# Rocketometer2148_MPU6050.net
KiCad netlist of a schematic drawn in EAGLE
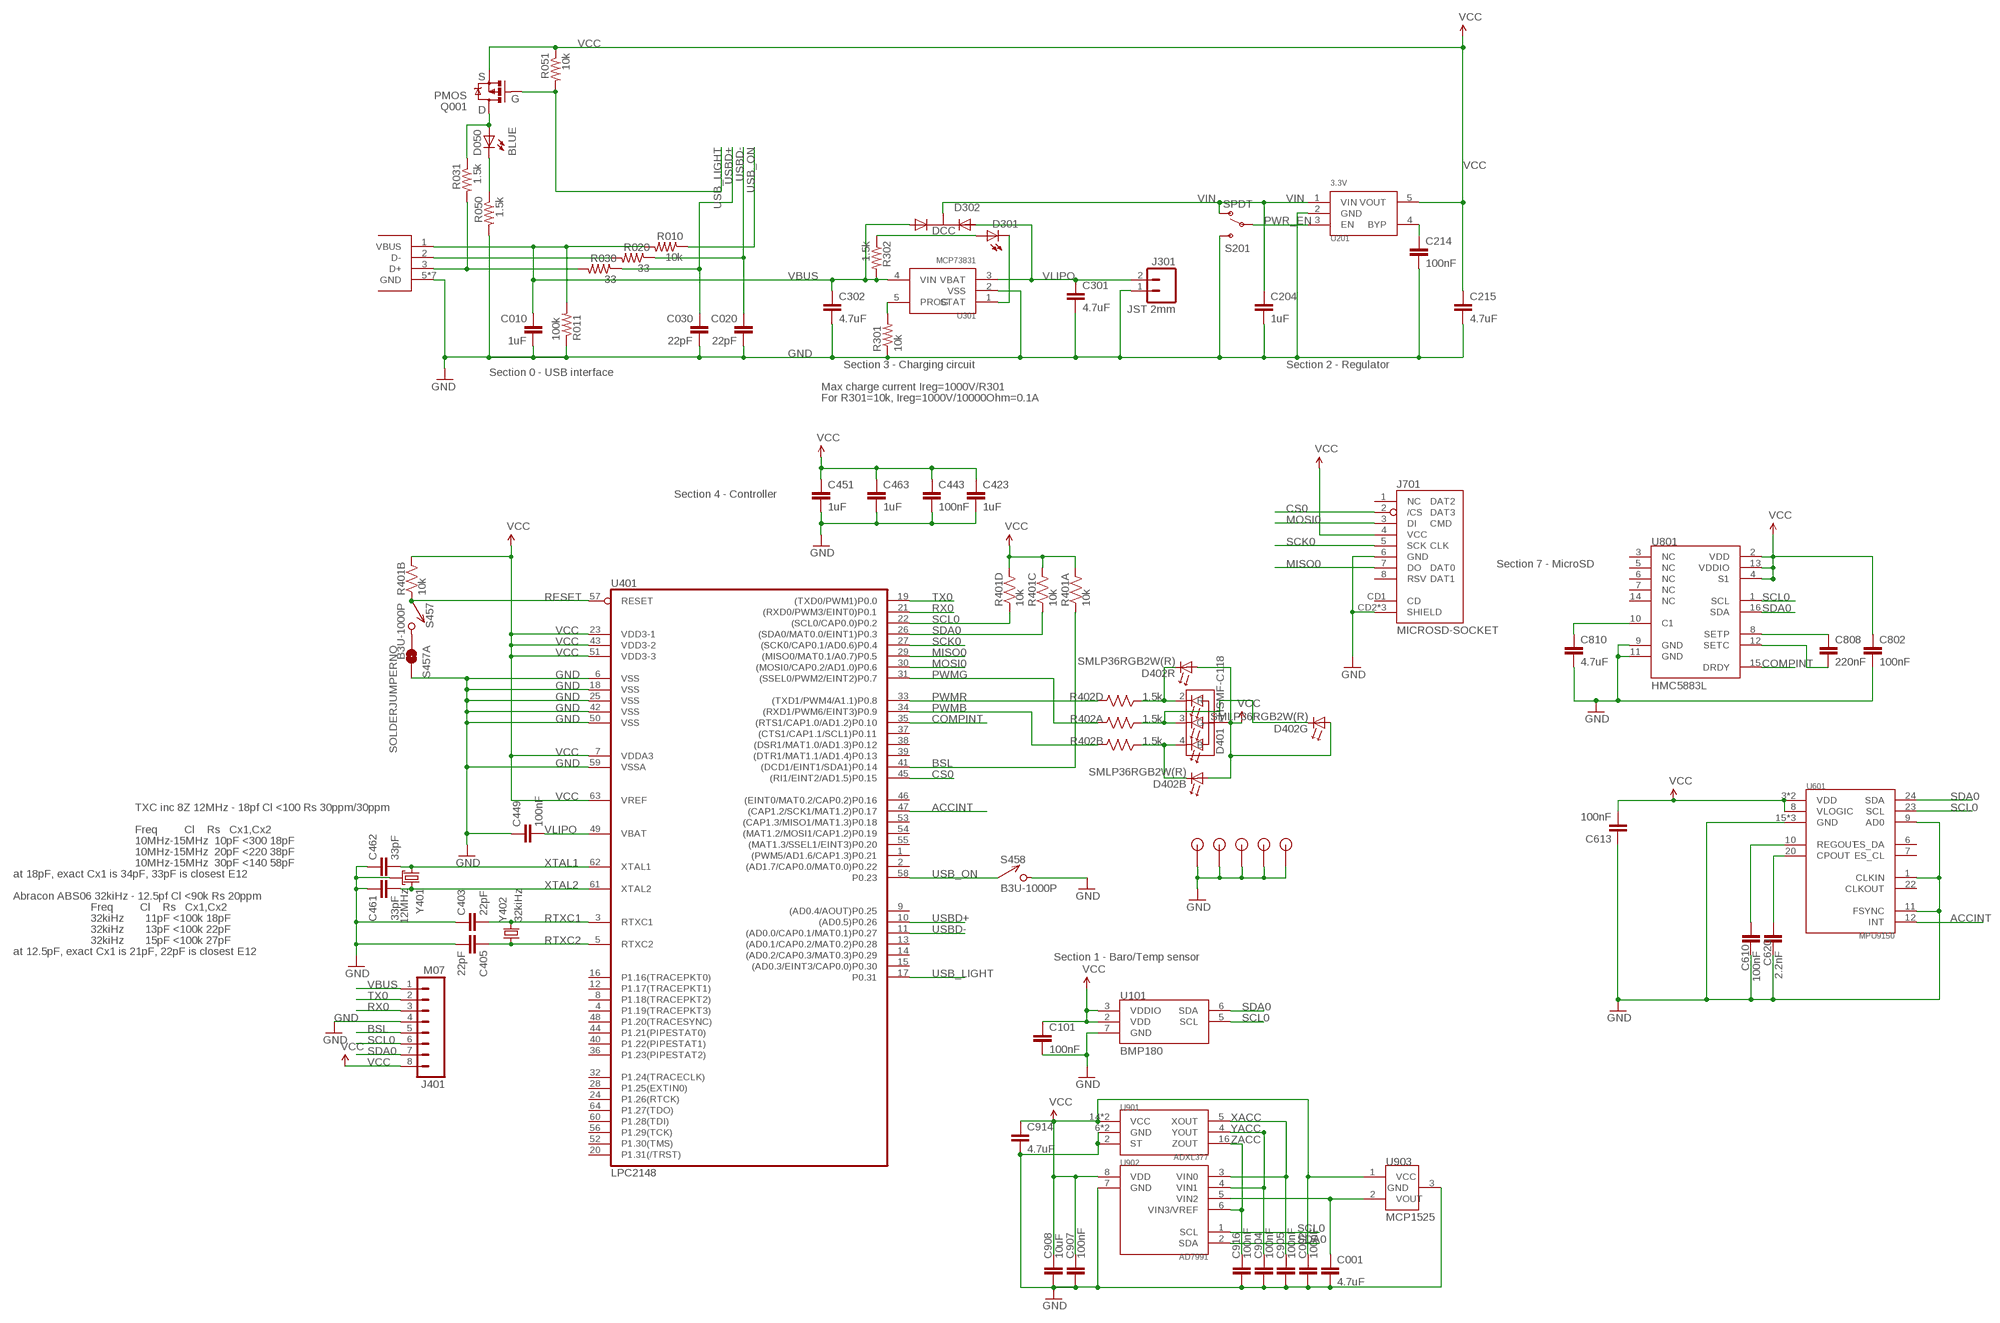
[diagram p0: schematic, sheet 1]

(export (version "E")
  (design (tool "Eeschema 10.0.6"))
  (components
    (comp (ref "C001")
      (value "4.7uF")
      (footprint "eagle-import:0402-CAP")
      (libsource (lib "eagle-import") (part "CAP0402-CAP"))
    )
    (comp (ref "C002")
      (value "100nF")
      (footprint "eagle-import:0402-CAP")
      (libsource (lib "eagle-import") (part "SparkFun-Passives_CAP0402-CAP"))
    )
    (comp (ref "C010")
      (value "1uF")
      (footprint "eagle-import:0402-CAP")
      (libsource (lib "eagle-import") (part "CAP0402-CAP"))
    )
    (comp (ref "C020")
      (value "22pF")
      (footprint "eagle-import:0402-CAP")
      (libsource (lib "eagle-import") (part "CAP0402-CAP"))
    )
    (comp (ref "C030")
      (value "22pF")
      (footprint "eagle-import:0402-CAP")
      (libsource (lib "eagle-import") (part "CAP0402-CAP"))
    )
    (comp (ref "C101")
      (value "100nF")
      (footprint "eagle-import:0402-CAP")
      (libsource (lib "eagle-import") (part "CAP0402-CAP"))
    )
    (comp (ref "C204")
      (value "1uF")
      (footprint "eagle-import:0402-CAP")
      (libsource (lib "eagle-import") (part "CAP0402-CAP"))
    )
    (comp (ref "C214")
      (value "100nF")
      (footprint "eagle-import:0402-CAP")
      (libsource (lib "eagle-import") (part "CAP0402-CAP"))
    )
    (comp (ref "C215")
      (value "4.7uF")
      (footprint "eagle-import:0402-CAP")
      (libsource (lib "eagle-import") (part "CAP0402-CAP"))
    )
    (comp (ref "C301")
      (value "4.7uF")
      (footprint "eagle-import:0402-CAP")
      (libsource (lib "eagle-import") (part "CAP0402-CAP"))
    )
    (comp (ref "C302")
      (value "4.7uF")
      (footprint "eagle-import:0402-CAP")
      (libsource (lib "eagle-import") (part "CAP0402-CAP"))
    )
    (comp (ref "C403")
      (value "22pF")
      (footprint "eagle-import:0402-CAP")
      (libsource (lib "eagle-import") (part "CAP0402-CAP"))
    )
    (comp (ref "C405")
      (value "22pF")
      (footprint "eagle-import:0402-CAP")
      (libsource (lib "eagle-import") (part "CAP0402-CAP"))
    )
    (comp (ref "C423")
      (value "1uF")
      (footprint "eagle-import:0402-CAP")
      (libsource (lib "eagle-import") (part "CAP0402-CAP"))
    )
    (comp (ref "C443")
      (value "100nF")
      (footprint "eagle-import:0402-CAP")
      (libsource (lib "eagle-import") (part "CAP0402-CAP"))
    )
    (comp (ref "C449")
      (value "100nF")
      (footprint "eagle-import:0402-CAP")
      (libsource (lib "eagle-import") (part "CAP0402-CAP"))
    )
    (comp (ref "C451")
      (value "1uF")
      (footprint "eagle-import:0402-CAP")
      (libsource (lib "eagle-import") (part "CAP0402-CAP"))
    )
    (comp (ref "C461")
      (value "33pF")
      (footprint "eagle-import:0402-CAP")
      (libsource (lib "eagle-import") (part "CAP0402-CAP"))
    )
    (comp (ref "C462")
      (value "33pF")
      (footprint "eagle-import:0402-CAP")
      (libsource (lib "eagle-import") (part "CAP0402-CAP"))
    )
    (comp (ref "C463")
      (value "1uF")
      (footprint "eagle-import:0402-CAP")
      (libsource (lib "eagle-import") (part "CAP0402-CAP"))
    )
    (comp (ref "C610")
      (value "100nF")
      (footprint "eagle-import:0402-CAP")
      (libsource (lib "eagle-import") (part "CAP0402-CAP"))
    )
    (comp (ref "C613")
      (value "100nF")
      (footprint "eagle-import:0402-CAP")
      (libsource (lib "eagle-import") (part "CAP0402-CAP"))
    )
    (comp (ref "C620")
      (value "2.2nF")
      (footprint "eagle-import:0402-CAP")
      (libsource (lib "eagle-import") (part "CAP0402-CAP"))
    )
    (comp (ref "C802")
      (value "100nF")
      (footprint "eagle-import:0402-CAP")
      (libsource (lib "eagle-import") (part "CAP0402-CAP"))
    )
    (comp (ref "C808")
      (value "220nF")
      (footprint "eagle-import:0402-CAP")
      (libsource (lib "eagle-import") (part "CAP0402-CAP"))
    )
    (comp (ref "C810")
      (value "4.7uF")
      (footprint "eagle-import:0402-CAP")
      (libsource (lib "eagle-import") (part "CAP0402-CAP"))
    )
    (comp (ref "C904")
      (value "100nF")
      (footprint "eagle-import:0402-CAP")
      (libsource (lib "eagle-import") (part "CAP0402-CAP"))
    )
    (comp (ref "C905")
      (value "100nF")
      (footprint "eagle-import:0402-CAP")
      (libsource (lib "eagle-import") (part "CAP0402-CAP"))
    )
    (comp (ref "C907")
      (value "100nF")
      (footprint "eagle-import:0402-CAP")
      (libsource (lib "eagle-import") (part "SparkFun-Passives_CAP0402-CAP"))
    )
    (comp (ref "C908")
      (value "10uF")
      (footprint "eagle-import:0603-CAP")
      (libsource (lib "eagle-import") (part "CAP0603-CAP"))
    )
    (comp (ref "C914")
      (value "4.7uF")
      (footprint "eagle-import:0402-CAP")
      (libsource (lib "eagle-import") (part "CAP0402-CAP"))
    )
    (comp (ref "C916")
      (value "100nF")
      (footprint "eagle-import:0402-CAP")
      (libsource (lib "eagle-import") (part "CAP0402-CAP"))
    )
    (comp (ref "D050")
      (value "BLUE")
      (footprint "eagle-import:LED-0603")
      (libsource (lib "eagle-import") (part "LED0603"))
    )
    (comp (ref "D301")
      (value "YELLOW")
      (footprint "eagle-import:LED-0603")
      (libsource (lib "eagle-import") (part "LED0603"))
    )
    (comp (ref "D302")
      (value "DCC")
      (footprint "eagle-import:SOT-23-3")
      (libsource (lib "eagle-import") (part "PMEG2005CT"))
    )
    (comp (ref "D401")
      (value "HSMF-C118")
      (footprint "eagle-import:HSMF-C118")
      (libsource (lib "eagle-import") (part "HSMF-C118"))
    )
    (comp (ref "D402")
      (value "SMLP36RGB2W(R)")
      (footprint "eagle-import:SMLP36")
      (libsource (lib "eagle-import") (part "SMLP36RGB2W(R)"))
    )
    (comp (ref "J001")
      (value "USB_MICROB_JST")
      (footprint "eagle-import:UB-MC5BR3-SD204-4S")
      (libsource (lib "eagle-import") (part "USB_MICROB_JST"))
    )
    (comp (ref "J301")
      (value "JST 2mm")
      (footprint "eagle-import:JST-2-SMD")
      (libsource (lib "eagle-import") (part "M02-JST-2MM-SMT"))
    )
    (comp (ref "J401")
      (value "M07")
      (footprint "eagle-import:1X08")
      (libsource (lib "eagle-import") (part "M081X08"))
    )
    (comp (ref "J701")
      (value "MICROSD-SOCKET")
      (footprint "eagle-import:MICROSD-SOCKET-PP")
      (libsource (lib "eagle-import") (part "MICROSD-SOCKET"))
    )
    (comp (ref "JP1")
      (value "STANDOFF")
      (footprint "eagle-import:STANDOFF")
      (libsource (lib "eagle-import") (part "STANDOFF"))
    )
    (comp (ref "JP2")
      (value "STANDOFF")
      (footprint "eagle-import:STANDOFF")
      (libsource (lib "eagle-import") (part "STANDOFF"))
    )
    (comp (ref "JP3")
      (value "STANDOFF")
      (footprint "eagle-import:STANDOFF")
      (libsource (lib "eagle-import") (part "STANDOFF"))
    )
    (comp (ref "JP4")
      (value "STANDOFF")
      (footprint "eagle-import:STANDOFF")
      (libsource (lib "eagle-import") (part "STANDOFF"))
    )
    (comp (ref "JP5")
      (value "STANDOFF")
      (footprint "eagle-import:STANDOFF")
      (libsource (lib "eagle-import") (part "STANDOFF"))
    )
    (comp (ref "Q001")
      (value "PMOS")
      (footprint "eagle-import:SOT23-3")
      (libsource (lib "eagle-import") (part "MOSFET-PCHANNELSMD"))
    )
    (comp (ref "R010")
      (value "10k")
      (footprint "eagle-import:0402-RES")
      (libsource (lib "eagle-import") (part "RESISTOR0402-RES"))
    )
    (comp (ref "R011")
      (value "100k")
      (footprint "eagle-import:0402-RES")
      (libsource (lib "eagle-import") (part "RESISTOR0402-RES"))
    )
    (comp (ref "R020")
      (value "33")
      (footprint "eagle-import:0402-RES")
      (libsource (lib "eagle-import") (part "RESISTOR0402-RES"))
    )
    (comp (ref "R030")
      (value "33")
      (footprint "eagle-import:0402-RES")
      (libsource (lib "eagle-import") (part "RESISTOR0402-RES"))
    )
    (comp (ref "R031")
      (value "1.5k")
      (footprint "eagle-import:0402-RES")
      (libsource (lib "eagle-import") (part "RESISTOR0402-RES"))
    )
    (comp (ref "R050")
      (value "1.5k")
      (footprint "eagle-import:0402-RES")
      (libsource (lib "eagle-import") (part "RESISTOR0402-RES"))
    )
    (comp (ref "R051")
      (value "10k")
      (footprint "eagle-import:0402-RES")
      (libsource (lib "eagle-import") (part "RESISTOR0402-RES"))
    )
    (comp (ref "R301")
      (value "10k")
      (footprint "eagle-import:0402-RES")
      (libsource (lib "eagle-import") (part "RESISTOR0402-RES"))
    )
    (comp (ref "R302")
      (value "1.5k")
      (footprint "eagle-import:0402-RES")
      (libsource (lib "eagle-import") (part "RESISTOR0402-RES"))
    )
    (comp (ref "R401")
      (value "10k")
      (footprint "eagle-import:CRA04")
      (fields (field (name "DIGIKEY") "CRA4S810KCT-ND"))
      (libsource (lib "eagle-import") (part "RP404"))
    )
    (comp (ref "R402")
      (value "1.5k")
      (footprint "eagle-import:CRA04")
      (fields (field (name "DIGIKEY") "CRA4S81.5KCT-ND"))
      (libsource (lib "eagle-import") (part "RP404"))
    )
    (comp (ref "S201")
      (value "SPDT")
      (footprint "eagle-import:AYZ0202")
      (libsource (lib "eagle-import") (part "SWITCH-SPSTSMD"))
    )
    (comp (ref "S457")
      (value "B3U-1000P")
      (footprint "eagle-import:B3U-1000P")
      (libsource (lib "eagle-import") (part "B3U-1000P"))
    )
    (comp (ref "S457A")
      (value "SOLDERJUMPERNO")
      (footprint "eagle-import:SJ_2S-NO")
      (libsource (lib "eagle-import") (part "SOLDERJUMPERNO"))
    )
    (comp (ref "S458")
      (value "B3U-1000P")
      (footprint "eagle-import:B3U-1000P")
      (libsource (lib "eagle-import") (part "B3U-1000P"))
    )
    (comp (ref "U101")
      (value "BMP180")
      (footprint "eagle-import:BMP180")
      (libsource (lib "eagle-import") (part "BMP180"))
    )
    (comp (ref "U201")
      (value "3.3V")
      (footprint "eagle-import:SOT-23-5")
      (libsource (lib "eagle-import") (part "MIC5319D5"))
    )
    (comp (ref "U301")
      (value "MCP73831")
      (footprint "eagle-import:SOT-23-5")
      (libsource (lib "eagle-import") (part "MCP73831"))
    )
    (comp (ref "U401")
      (value "LPC2148")
      (footprint "eagle-import:SQFP-S-10X10-64")
      (libsource (lib "eagle-import") (part "LPC213X"))
    )
    (comp (ref "U601")
      (value "MPU9150")
      (footprint "eagle-import:LLGA24")
      (libsource (lib "eagle-import") (part "MPU9150"))
    )
    (comp (ref "U801")
      (value "HMC5883L")
      (footprint "eagle-import:16LPCC")
      (libsource (lib "eagle-import") (part "HMC5883LSMD"))
    )
    (comp (ref "U901")
      (value "ADXL377")
      (footprint "eagle-import:ADXL377")
      (libsource (lib "eagle-import") (part "ADXL377"))
    )
    (comp (ref "U902")
      (value "AD7991")
      (footprint "eagle-import:SOT-23-8")
      (libsource (lib "eagle-import") (part "AD799X"))
    )
    (comp (ref "U903")
      (value "MCP1525")
      (footprint "eagle-import:SOT-23-3")
      (libsource (lib "eagle-import") (part "MCP1525"))
    )
    (comp (ref "Y401")
      (value "12MHz")
      (footprint "eagle-import:CRYSTAL_SMD_2MM_2_5MM")
      (libsource (lib "eagle-import") (part "CX2520"))
    )
    (comp (ref "Y402")
      (value "32kiHz")
      (footprint "eagle-import:ABS06")
      (libsource (lib "eagle-import") (part "ABS06"))
    )
  )
  (nets
    (net (code "1") (name "/ACCINT") (class "Default")
      (node (ref "U401") (pin "47") (pinfunction "(CAP1.2/SCK1/MAT1.2)P0.17_47") (pintype "bidirectional"))
      (node (ref "U601") (pin "12") (pinfunction "INT_12") (pintype "bidirectional"))
    )
    (net (code "2") (name "/BSL") (class "Default")
      (node (ref "J401") (pin "5") (pinfunction "5_5") (pintype "passive"))
      (node (ref "R401") (pin "1") (pinfunction "1_1") (pintype "passive"))
      (node (ref "U401") (pin "41") (pinfunction "(DCD1/EINT1/SDA1)P0.14_41") (pintype "bidirectional"))
    )
    (net (code "3") (name "/COMPINT") (class "Default")
      (node (ref "U401") (pin "35") (pinfunction "(RTS1/CAP1.0/AD1.2)P0.10_35") (pintype "bidirectional"))
      (node (ref "U801") (pin "15") (pinfunction "DRDY_15") (pintype "bidirectional"))
    )
    (net (code "4") (name "/CS0") (class "Default")
      (node (ref "J701") (pin "2") (pinfunction "/CS_2") (pintype "bidirectional"))
      (node (ref "U401") (pin "45") (pinfunction "(RI1/EINT2/AD1.5)P0.15_45") (pintype "bidirectional"))
    )
    (net (code "5") (name "/MISO0") (class "Default")
      (node (ref "J701") (pin "7") (pinfunction "DO_7") (pintype "bidirectional"))
      (node (ref "U401") (pin "29") (pinfunction "(MISO0/MAT0.1/A0.7)P0.5_29") (pintype "bidirectional"))
    )
    (net (code "6") (name "/MOSI0") (class "Default")
      (node (ref "J701") (pin "3") (pinfunction "DI_3") (pintype "bidirectional"))
      (node (ref "U401") (pin "30") (pinfunction "(MOSI0/CAP0.2/AD1.0)P0.6_30") (pintype "bidirectional"))
    )
    (net (code "7") (name "/PWMB") (class "Default")
      (node (ref "R402") (pin "7") (pinfunction "2_7") (pintype "passive"))
      (node (ref "U401") (pin "34") (pinfunction "(RXD1/PWM6/EINT3)P0.9_34") (pintype "bidirectional"))
    )
    (net (code "8") (name "/PWMG") (class "Default")
      (node (ref "R402") (pin "8") (pinfunction "2_8") (pintype "passive"))
      (node (ref "U401") (pin "31") (pinfunction "(SSEL0/PWM2/EINT2)P0.7_31") (pintype "bidirectional"))
    )
    (net (code "9") (name "/PWMR") (class "Default")
      (node (ref "R402") (pin "5") (pinfunction "2_5") (pintype "passive"))
      (node (ref "U401") (pin "33") (pinfunction "(TXD1/PWM4/A1.1)P0.8_33") (pintype "bidirectional"))
    )
    (net (code "10") (name "/PWR_EN") (class "Default")
      (node (ref "S201") (pin "2") (pinfunction "P_2") (pintype "passive"))
      (node (ref "U201") (pin "3") (pinfunction "EN_3") (pintype "bidirectional"))
    )
    (net (code "11") (name "/RESET") (class "Default")
      (node (ref "R401") (pin "2") (pinfunction "1_2") (pintype "passive"))
      (node (ref "S457") (pin "P$1") (pinfunction "1_P$1") (pintype "bidirectional"))
      (node (ref "U401") (pin "57") (pinfunction "RESET_57") (pintype "input"))
    )
    (net (code "12") (name "/RTXC1") (class "Default")
      (node (ref "C403") (pin "2") (pinfunction "2_2") (pintype "passive"))
      (node (ref "U401") (pin "3") (pinfunction "RTXC1_3") (pintype "input"))
      (node (ref "Y402") (pin "2") (pinfunction "2_2") (pintype "passive"))
    )
    (net (code "13") (name "/RTXC2") (class "Default")
      (node (ref "C405") (pin "1") (pinfunction "1_1") (pintype "passive"))
      (node (ref "U401") (pin "5") (pinfunction "RTXC2_5") (pintype "output"))
      (node (ref "Y402") (pin "1") (pinfunction "1_1") (pintype "passive"))
    )
    (net (code "14") (name "/RX0") (class "Default")
      (node (ref "J401") (pin "3") (pinfunction "3_3") (pintype "passive"))
      (node (ref "U401") (pin "21") (pinfunction "(RXD0/PWM3/EINT0)P0.1_21") (pintype "bidirectional"))
    )
    (net (code "15") (name "/SCK0") (class "Default")
      (node (ref "J701") (pin "5") (pinfunction "SCK_5") (pintype "bidirectional"))
      (node (ref "U401") (pin "27") (pinfunction "(SCK0/CAP0.1/AD0.6)P0.4_27") (pintype "bidirectional"))
    )
    (net (code "16") (name "/SCL0") (class "Default")
      (node (ref "J401") (pin "6") (pinfunction "6_6") (pintype "passive"))
      (node (ref "R401") (pin "4") (pinfunction "1_4") (pintype "passive"))
      (node (ref "U101") (pin "5") (pinfunction "SCL_5") (pintype "input"))
      (node (ref "U401") (pin "22") (pinfunction "(SCL0/CAP0.0)P0.2_22") (pintype "bidirectional"))
      (node (ref "U601") (pin "23") (pinfunction "SCL_23") (pintype "bidirectional"))
      (node (ref "U801") (pin "1") (pinfunction "SCL_1") (pintype "bidirectional"))
      (node (ref "U902") (pin "1") (pinfunction "SCL_1") (pintype "bidirectional"))
    )
    (net (code "17") (name "/SDA0") (class "Default")
      (node (ref "J401") (pin "7") (pinfunction "7_7") (pintype "passive"))
      (node (ref "R401") (pin "3") (pinfunction "1_3") (pintype "passive"))
      (node (ref "U101") (pin "6") (pinfunction "SDA_6") (pintype "bidirectional"))
      (node (ref "U401") (pin "26") (pinfunction "(SDA0/MAT0.0/EINT1)P0.3_26") (pintype "bidirectional"))
      (node (ref "U601") (pin "24") (pinfunction "SDA_24") (pintype "bidirectional"))
      (node (ref "U801") (pin "16") (pinfunction "SDA_16") (pintype "bidirectional"))
      (node (ref "U902") (pin "2") (pinfunction "SDA_2") (pintype "bidirectional"))
    )
    (net (code "18") (name "/TX0") (class "Default")
      (node (ref "J401") (pin "2") (pinfunction "2_2") (pintype "passive"))
      (node (ref "U401") (pin "19") (pinfunction "(TXD0/PWM1)P0.0_19") (pintype "bidirectional"))
    )
    (net (code "19") (name "/USBD+") (class "Default")
      (node (ref "C030") (pin "1") (pinfunction "1_1") (pintype "passive"))
      (node (ref "R030") (pin "1") (pinfunction "1_1") (pintype "passive"))
      (node (ref "U401") (pin "10") (pinfunction "(AD0.5)P0.26_10") (pintype "bidirectional"))
    )
    (net (code "20") (name "/USBD-") (class "Default")
      (node (ref "C020") (pin "1") (pinfunction "1_1") (pintype "passive"))
      (node (ref "R020") (pin "1") (pinfunction "1_1") (pintype "passive"))
      (node (ref "U401") (pin "11") (pinfunction "(AD0.0/CAP0.1/MAT0.1)P0.27_11") (pintype "bidirectional"))
    )
    (net (code "21") (name "/USB_LIGHT") (class "Default")
      (node (ref "Q001") (pin "1") (pinfunction "G_1") (pintype "passive"))
      (node (ref "R051") (pin "2") (pinfunction "2_2") (pintype "passive"))
      (node (ref "U401") (pin "17") (pinfunction "P0.31_17") (pintype "output"))
    )
    (net (code "22") (name "/USB_ON") (class "Default")
      (node (ref "R010") (pin "1") (pinfunction "1_1") (pintype "passive"))
      (node (ref "S458") (pin "P$1") (pinfunction "1_P$1") (pintype "bidirectional"))
      (node (ref "U401") (pin "58") (pinfunction "P0.23_58") (pintype "bidirectional"))
    )
    (net (code "23") (name "/VBUS") (class "Default")
      (node (ref "C010") (pin "1") (pinfunction "1_1") (pintype "passive"))
      (node (ref "C302") (pin "1") (pinfunction "1_1") (pintype "passive"))
      (node (ref "D302") (pin "1") (pinfunction "A1_1") (pintype "passive"))
      (node (ref "J001") (pin "1") (pinfunction "VBUS_1") (pintype "bidirectional"))
      (node (ref "J401") (pin "1") (pinfunction "1_1") (pintype "passive"))
      (node (ref "R010") (pin "2") (pinfunction "2_2") (pintype "passive"))
      (node (ref "R011") (pin "2") (pinfunction "2_2") (pintype "passive"))
      (node (ref "R302") (pin "2") (pinfunction "2_2") (pintype "passive"))
      (node (ref "U301") (pin "4") (pinfunction "VIN_4") (pintype "power_in"))
    )
    (net (code "24") (name "/VIN") (class "Default")
      (node (ref "C204") (pin "1") (pinfunction "1_1") (pintype "passive"))
      (node (ref "D302") (pin "3") (pinfunction "K_3") (pintype "passive"))
      (node (ref "S201") (pin "1") (pinfunction "O_1") (pintype "passive"))
      (node (ref "U201") (pin "1") (pinfunction "VIN_1") (pintype "bidirectional"))
    )
    (net (code "25") (name "/VLIPO") (class "Default")
      (node (ref "C301") (pin "1") (pinfunction "1_1") (pintype "passive"))
      (node (ref "C449") (pin "2") (pinfunction "2_2") (pintype "passive"))
      (node (ref "D302") (pin "2") (pinfunction "A2_2") (pintype "passive"))
      (node (ref "J301") (pin "2") (pinfunction "2_2") (pintype "passive"))
      (node (ref "U301") (pin "3") (pinfunction "VBAT_3") (pintype "power_in"))
      (node (ref "U401") (pin "49") (pinfunction "VBAT_49") (pintype "power_in"))
    )
    (net (code "26") (name "/XACC") (class "Default")
      (node (ref "C905") (pin "1") (pinfunction "1_1") (pintype "passive"))
      (node (ref "U901") (pin "5") (pinfunction "XOUT_5") (pintype "bidirectional"))
      (node (ref "U902") (pin "3") (pinfunction "VIN0_3") (pintype "bidirectional"))
    )
    (net (code "27") (name "/XTAL1") (class "Default")
      (node (ref "C462") (pin "2") (pinfunction "2_2") (pintype "passive"))
      (node (ref "U401") (pin "62") (pinfunction "XTAL1_62") (pintype "input"))
      (node (ref "Y401") (pin "1") (pinfunction "1_1") (pintype "passive"))
    )
    (net (code "28") (name "/XTAL2") (class "Default")
      (node (ref "C461") (pin "2") (pinfunction "2_2") (pintype "passive"))
      (node (ref "U401") (pin "61") (pinfunction "XTAL2_61") (pintype "output"))
      (node (ref "Y401") (pin "3") (pinfunction "2_3") (pintype "passive"))
    )
    (net (code "29") (name "/YACC") (class "Default")
      (node (ref "C904") (pin "1") (pinfunction "1_1") (pintype "passive"))
      (node (ref "U901") (pin "4") (pinfunction "YOUT_4") (pintype "bidirectional"))
      (node (ref "U902") (pin "4") (pinfunction "VIN1_4") (pintype "bidirectional"))
    )
    (net (code "30") (name "/ZACC") (class "Default")
      (node (ref "C916") (pin "1") (pinfunction "1_1") (pintype "passive"))
      (node (ref "U901") (pin "16") (pinfunction "ZOUT_16") (pintype "bidirectional"))
      (node (ref "U902") (pin "6") (pinfunction "VIN3/VREF_6") (pintype "bidirectional"))
    )
    (net (code "31") (name "GND") (class "Default")
      (node (ref "C001") (pin "2") (pinfunction "2_2") (pintype "passive"))
      (node (ref "C002") (pin "2") (pinfunction "2_2") (pintype "passive"))
      (node (ref "C010") (pin "2") (pinfunction "2_2") (pintype "passive"))
      (node (ref "C020") (pin "2") (pinfunction "2_2") (pintype "passive"))
      (node (ref "C030") (pin "2") (pinfunction "2_2") (pintype "passive"))
      (node (ref "C101") (pin "2") (pinfunction "2_2") (pintype "passive"))
      (node (ref "C204") (pin "2") (pinfunction "2_2") (pintype "passive"))
      (node (ref "C214") (pin "2") (pinfunction "2_2") (pintype "passive"))
      (node (ref "C215") (pin "2") (pinfunction "2_2") (pintype "passive"))
      (node (ref "C301") (pin "2") (pinfunction "2_2") (pintype "passive"))
      (node (ref "C302") (pin "2") (pinfunction "2_2") (pintype "passive"))
      (node (ref "C403") (pin "1") (pinfunction "1_1") (pintype "passive"))
      (node (ref "C405") (pin "2") (pinfunction "2_2") (pintype "passive"))
      (node (ref "C423") (pin "2") (pinfunction "2_2") (pintype "passive"))
      (node (ref "C443") (pin "2") (pinfunction "2_2") (pintype "passive"))
      (node (ref "C449") (pin "1") (pinfunction "1_1") (pintype "passive"))
      (node (ref "C451") (pin "2") (pinfunction "2_2") (pintype "passive"))
      (node (ref "C461") (pin "1") (pinfunction "1_1") (pintype "passive"))
      (node (ref "C462") (pin "1") (pinfunction "1_1") (pintype "passive"))
      (node (ref "C463") (pin "2") (pinfunction "2_2") (pintype "passive"))
      (node (ref "C610") (pin "2") (pinfunction "2_2") (pintype "passive"))
      (node (ref "C613") (pin "1") (pinfunction "1_1") (pintype "passive"))
      (node (ref "C620") (pin "1") (pinfunction "1_1") (pintype "passive"))
      (node (ref "C802") (pin "2") (pinfunction "2_2") (pintype "passive"))
      (node (ref "C810") (pin "2") (pinfunction "2_2") (pintype "passive"))
      (node (ref "C904") (pin "2") (pinfunction "2_2") (pintype "passive"))
      (node (ref "C905") (pin "2") (pinfunction "2_2") (pintype "passive"))
      (node (ref "C907") (pin "2") (pinfunction "2_2") (pintype "passive"))
      (node (ref "C908") (pin "2") (pinfunction "2_2") (pintype "passive"))
      (node (ref "C914") (pin "2") (pinfunction "2_2") (pintype "passive"))
      (node (ref "C916") (pin "2") (pinfunction "2_2") (pintype "passive"))
      (node (ref "J001") (pin "5") (pinfunction "GND_5") (pintype "bidirectional"))
      (node (ref "J001") (pin "P$10") (pinfunction "GND_P$10") (pintype "bidirectional"))
      (node (ref "J001") (pin "P$11") (pinfunction "GND_P$11") (pintype "bidirectional"))
      (node (ref "J001") (pin "P$6") (pinfunction "GND_P$6") (pintype "bidirectional"))
      (node (ref "J001") (pin "P$7") (pinfunction "GND_P$7") (pintype "bidirectional"))
      (node (ref "J001") (pin "P$8") (pinfunction "GND_P$8") (pintype "bidirectional"))
      (node (ref "J001") (pin "P$9") (pinfunction "GND_P$9") (pintype "bidirectional"))
      (node (ref "J301") (pin "1") (pinfunction "1_1") (pintype "passive"))
      (node (ref "J401") (pin "4") (pinfunction "4_4") (pintype "passive"))
      (node (ref "J701") (pin "6") (pinfunction "GND_6") (pintype "bidirectional"))
      (node (ref "J701") (pin "CD2") (pinfunction "SHIELD_CD2") (pintype "bidirectional"))
      (node (ref "J701") (pin "GND1") (pinfunction "SHIELD_GND1") (pintype "bidirectional"))
      (node (ref "J701") (pin "GND3") (pinfunction "SHIELD_GND3") (pintype "bidirectional"))
      (node (ref "JP1") (pin "P$1") (pinfunction "P$1_P$1") (pintype "bidirectional"))
      (node (ref "JP2") (pin "P$1") (pinfunction "P$1_P$1") (pintype "bidirectional"))
      (node (ref "JP3") (pin "P$1") (pinfunction "P$1_P$1") (pintype "bidirectional"))
      (node (ref "JP4") (pin "P$1") (pinfunction "P$1_P$1") (pintype "bidirectional"))
      (node (ref "JP5") (pin "P$1") (pinfunction "P$1_P$1") (pintype "bidirectional"))
      (node (ref "R011") (pin "1") (pinfunction "1_1") (pintype "passive"))
      (node (ref "R050") (pin "2") (pinfunction "2_2") (pintype "passive"))
      (node (ref "R301") (pin "1") (pinfunction "1_1") (pintype "passive"))
      (node (ref "S201") (pin "3") (pinfunction "S_3") (pintype "passive"))
      (node (ref "S457A") (pin "2") (pinfunction "2_2") (pintype "passive"))
      (node (ref "S458") (pin "P$2") (pinfunction "2_P$2") (pintype "bidirectional"))
      (node (ref "U101") (pin "7") (pinfunction "GND_7") (pintype "power_in"))
      (node (ref "U201") (pin "2") (pinfunction "GND_2") (pintype "bidirectional"))
      (node (ref "U301") (pin "2") (pinfunction "VSS_2") (pintype "power_in"))
      (node (ref "U401") (pin "18") (pinfunction "VSS_18") (pintype "power_in"))
      (node (ref "U401") (pin "25") (pinfunction "VSS_25") (pintype "power_in"))
      (node (ref "U401") (pin "42") (pinfunction "VSS_42") (pintype "power_in"))
      (node (ref "U401") (pin "50") (pinfunction "VSS_50") (pintype "power_in"))
      (node (ref "U401") (pin "59") (pinfunction "VSSA_59") (pintype "power_in"))
      (node (ref "U401") (pin "6") (pinfunction "VSS_6") (pintype "power_in"))
      (node (ref "U601") (pin "1") (pinfunction "CLKIN_1") (pintype "bidirectional"))
      (node (ref "U601") (pin "11") (pinfunction "FSYNC_11") (pintype "bidirectional"))
      (node (ref "U601") (pin "15") (pinfunction "GND_15") (pintype "bidirectional"))
      (node (ref "U601") (pin "17") (pinfunction "GND_17") (pintype "bidirectional"))
      (node (ref "U601") (pin "18") (pinfunction "GND_18") (pintype "bidirectional"))
      (node (ref "U601") (pin "9") (pinfunction "AD0_9") (pintype "bidirectional"))
      (node (ref "U801") (pin "11") (pinfunction "GND_11") (pintype "bidirectional"))
      (node (ref "U801") (pin "9") (pinfunction "GND_9") (pintype "bidirectional"))
      (node (ref "U901") (pin "2") (pinfunction "ST_2") (pintype "bidirectional"))
      (node (ref "U901") (pin "6") (pinfunction "GND_6") (pintype "bidirectional"))
      (node (ref "U901") (pin "7") (pinfunction "GND_7") (pintype "bidirectional"))
      (node (ref "U902") (pin "7") (pinfunction "GND_7") (pintype "bidirectional"))
      (node (ref "U903") (pin "3") (pinfunction "GND_3") (pintype "bidirectional"))
      (node (ref "Y401") (pin "2") (pinfunction "GND_2") (pintype "passive"))
      (node (ref "Y401") (pin "4") (pinfunction "GND_4") (pintype "passive"))
    )
    (net (code "32") (name "Net-(D050-PadC)") (class "Default")
      (node (ref "D050") (pin "C") (pinfunction "C_C") (pintype "passive"))
      (node (ref "R050") (pin "1") (pinfunction "1_1") (pintype "passive"))
    )
    (net (code "33") (name "Net-(D301-PadA)") (class "Default")
      (node (ref "D301") (pin "A") (pinfunction "A_A") (pintype "passive"))
      (node (ref "R302") (pin "1") (pinfunction "1_1") (pintype "passive"))
    )
    (net (code "34") (name "Net-(D401-B)") (class "Default")
      (node (ref "D401") (pin "4") (pinfunction "B_4") (pintype "passive"))
      (node (ref "D402") (pin "1") (pinfunction "C_1") (pintype "passive"))
      (node (ref "R402") (pin "2") (pinfunction "1_2") (pintype "passive"))
    )
    (net (code "35") (name "Net-(D401-G)") (class "Default")
      (node (ref "D401") (pin "3") (pinfunction "G_3") (pintype "passive"))
      (node (ref "D402") (pin "3") (pinfunction "C_3") (pintype "passive"))
      (node (ref "R402") (pin "1") (pinfunction "1_1") (pintype "passive"))
    )
    (net (code "36") (name "Net-(D401-R)") (class "Default")
      (node (ref "D401") (pin "2") (pinfunction "R_2") (pintype "passive"))
      (node (ref "D402") (pin "5") (pinfunction "C_5") (pintype "passive"))
      (node (ref "R402") (pin "4") (pinfunction "1_4") (pintype "passive"))
    )
    (net (code "37") (name "Net-(J001-D+)") (class "Default")
      (node (ref "J001") (pin "3") (pinfunction "D+_3") (pintype "bidirectional"))
      (node (ref "R030") (pin "2") (pinfunction "2_2") (pintype "passive"))
      (node (ref "R031") (pin "2") (pinfunction "2_2") (pintype "passive"))
    )
    (net (code "38") (name "Net-(J001-D-)") (class "Default")
      (node (ref "J001") (pin "2") (pinfunction "D-_2") (pintype "bidirectional"))
      (node (ref "R020") (pin "2") (pinfunction "2_2") (pintype "passive"))
    )
    (net (code "39") (name "Net-(Q001-D)") (class "Default")
      (node (ref "D050") (pin "A") (pinfunction "A_A") (pintype "passive"))
      (node (ref "Q001") (pin "3") (pinfunction "D_3") (pintype "passive"))
      (node (ref "R031") (pin "1") (pinfunction "1_1") (pintype "passive"))
    )
    (net (code "40") (name "Net-(S457-2)") (class "Default")
      (node (ref "S457") (pin "P$2") (pinfunction "2_P$2") (pintype "bidirectional"))
      (node (ref "S457A") (pin "1") (pinfunction "1_1") (pintype "passive"))
    )
    (net (code "41") (name "Net-(U201-BYP)") (class "Default")
      (node (ref "C214") (pin "1") (pinfunction "1_1") (pintype "passive"))
      (node (ref "U201") (pin "4") (pinfunction "BYP_4") (pintype "bidirectional"))
    )
    (net (code "42") (name "Net-(U301-PROG)") (class "Default")
      (node (ref "R301") (pin "2") (pinfunction "2_2") (pintype "passive"))
      (node (ref "U301") (pin "5") (pinfunction "PROG_5") (pintype "passive"))
    )
    (net (code "43") (name "Net-(U301-STAT)") (class "Default")
      (node (ref "D301") (pin "C") (pinfunction "C_C") (pintype "passive"))
      (node (ref "U301") (pin "1") (pinfunction "STAT_1") (pintype "bidirectional"))
    )
    (net (code "44") (name "Net-(U601-CPOUT)") (class "Default")
      (node (ref "C620") (pin "2") (pinfunction "2_2") (pintype "passive"))
      (node (ref "U601") (pin "20") (pinfunction "CPOUT_20") (pintype "bidirectional"))
    )
    (net (code "45") (name "Net-(U601-REGOUT)") (class "Default")
      (node (ref "C610") (pin "1") (pinfunction "1_1") (pintype "passive"))
      (node (ref "U601") (pin "10") (pinfunction "REGOUT_10") (pintype "bidirectional"))
    )
    (net (code "46") (name "Net-(U801-C1)") (class "Default")
      (node (ref "C810") (pin "1") (pinfunction "1_1") (pintype "passive"))
      (node (ref "U801") (pin "10") (pinfunction "C1_10") (pintype "bidirectional"))
    )
    (net (code "47") (name "Net-(U801-SETC)") (class "Default")
      (node (ref "C808") (pin "2") (pinfunction "2_2") (pintype "passive"))
      (node (ref "U801") (pin "12") (pinfunction "SETC_12") (pintype "bidirectional"))
    )
    (net (code "48") (name "Net-(U801-SETP)") (class "Default")
      (node (ref "C808") (pin "1") (pinfunction "1_1") (pintype "passive"))
      (node (ref "U801") (pin "8") (pinfunction "SETP_8") (pintype "bidirectional"))
    )
    (net (code "49") (name "Net-(U902-VIN2)") (class "Default")
      (node (ref "C001") (pin "1") (pinfunction "1_1") (pintype "passive"))
      (node (ref "U902") (pin "5") (pinfunction "VIN2_5") (pintype "bidirectional"))
      (node (ref "U903") (pin "2") (pinfunction "VOUT_2") (pintype "bidirectional"))
    )
    (net (code "50") (name "VCC") (class "Default")
      (node (ref "C002") (pin "1") (pinfunction "1_1") (pintype "passive"))
      (node (ref "C101") (pin "1") (pinfunction "1_1") (pintype "passive"))
      (node (ref "C215") (pin "1") (pinfunction "1_1") (pintype "passive"))
      (node (ref "C423") (pin "1") (pinfunction "1_1") (pintype "passive"))
      (node (ref "C443") (pin "1") (pinfunction "1_1") (pintype "passive"))
      (node (ref "C451") (pin "1") (pinfunction "1_1") (pintype "passive"))
      (node (ref "C463") (pin "1") (pinfunction "1_1") (pintype "passive"))
      (node (ref "C613") (pin "2") (pinfunction "2_2") (pintype "passive"))
      (node (ref "C802") (pin "1") (pinfunction "1_1") (pintype "passive"))
      (node (ref "C907") (pin "1") (pinfunction "1_1") (pintype "passive"))
      (node (ref "C908") (pin "1") (pinfunction "1_1") (pintype "passive"))
      (node (ref "C914") (pin "1") (pinfunction "1_1") (pintype "passive"))
      (node (ref "D401") (pin "1") (pinfunction "A_1") (pintype "passive"))
      (node (ref "D402") (pin "2") (pinfunction "A_2") (pintype "passive"))
      (node (ref "D402") (pin "4") (pinfunction "A_4") (pintype "passive"))
      (node (ref "D402") (pin "6") (pinfunction "A_6") (pintype "passive"))
      (node (ref "J401") (pin "8") (pinfunction "8_8") (pintype "passive"))
      (node (ref "J701") (pin "4") (pinfunction "VCC_4") (pintype "bidirectional"))
      (node (ref "Q001") (pin "2") (pinfunction "S_2") (pintype "passive"))
      (node (ref "R051") (pin "1") (pinfunction "1_1") (pintype "passive"))
      (node (ref "R401") (pin "5") (pinfunction "2_5") (pintype "passive"))
      (node (ref "R401") (pin "6") (pinfunction "2_6") (pintype "passive"))
      (node (ref "R401") (pin "7") (pinfunction "2_7") (pintype "passive"))
      (node (ref "R401") (pin "8") (pinfunction "2_8") (pintype "passive"))
      (node (ref "U101") (pin "2") (pinfunction "VDD_2") (pintype "power_in"))
      (node (ref "U101") (pin "3") (pinfunction "VDDIO_3") (pintype "power_in"))
      (node (ref "U201") (pin "5") (pinfunction "VOUT_5") (pintype "bidirectional"))
      (node (ref "U401") (pin "23") (pinfunction "VDD3-1_23") (pintype "power_in"))
      (node (ref "U401") (pin "43") (pinfunction "VDD3-2_43") (pintype "power_in"))
      (node (ref "U401") (pin "51") (pinfunction "VDD3-3_51") (pintype "power_in"))
      (node (ref "U401") (pin "63") (pinfunction "VREF_63") (pintype "input"))
      (node (ref "U401") (pin "7") (pinfunction "VDDA3_7") (pintype "power_in"))
      (node (ref "U601") (pin "13") (pinfunction "VDD_13") (pintype "bidirectional"))
      (node (ref "U601") (pin "3") (pinfunction "VDD_3") (pintype "bidirectional"))
      (node (ref "U601") (pin "8") (pinfunction "VLOGIC_8") (pintype "bidirectional"))
      (node (ref "U801") (pin "13") (pinfunction "VDDIO_13") (pintype "bidirectional"))
      (node (ref "U801") (pin "2") (pinfunction "VDD_2") (pintype "bidirectional"))
      (node (ref "U801") (pin "4") (pinfunction "S1_4") (pintype "bidirectional"))
      (node (ref "U901") (pin "14") (pinfunction "VCC_14") (pintype "bidirectional"))
      (node (ref "U901") (pin "15") (pinfunction "VCC_15") (pintype "bidirectional"))
      (node (ref "U902") (pin "8") (pinfunction "VDD_8") (pintype "bidirectional"))
      (node (ref "U903") (pin "1") (pinfunction "VCC_1") (pintype "bidirectional"))
    )
    (net (code "51") (name "unconnected-(J701-CD-PadCD1)") (class "Default")
      (node (ref "J701") (pin "CD1") (pinfunction "CD_CD1") (pintype "bidirectional"))
    )
    (net (code "52") (name "unconnected-(J701-NC-Pad1)") (class "Default")
      (node (ref "J701") (pin "1") (pinfunction "NC_1") (pintype "bidirectional"))
    )
    (net (code "53") (name "unconnected-(J701-RSV-Pad8)") (class "Default")
      (node (ref "J701") (pin "8") (pinfunction "RSV_8") (pintype "bidirectional"))
    )
    (net (code "54") (name "unconnected-(U401-(AD0.1{slash}CAP0.2{slash}MAT0.2)P0.28-Pad13)") (class "Default")
      (node (ref "U401") (pin "13") (pinfunction "(AD0.1/CAP0.2/MAT0.2)P0.28_13") (pintype "bidirectional"))
    )
    (net (code "55") (name "unconnected-(U401-(AD0.2{slash}CAP0.3{slash}MAT0.3)P0.29-Pad14)") (class "Default")
      (node (ref "U401") (pin "14") (pinfunction "(AD0.2/CAP0.3/MAT0.3)P0.29_14") (pintype "bidirectional"))
    )
    (net (code "56") (name "unconnected-(U401-(AD0.3{slash}EINT3{slash}CAP0.0)P0.30-Pad15)") (class "Default")
      (node (ref "U401") (pin "15") (pinfunction "(AD0.3/EINT3/CAP0.0)P0.30_15") (pintype "bidirectional"))
    )
    (net (code "57") (name "unconnected-(U401-(AD0.4{slash}AOUT)P0.25-Pad9)") (class "Default")
      (node (ref "U401") (pin "9") (pinfunction "(AD0.4/AOUT)P0.25_9") (pintype "bidirectional"))
    )
    (net (code "58") (name "unconnected-(U401-(AD1.7{slash}CAP0.0{slash}MAT0.0)P0.22-Pad2)") (class "Default")
      (node (ref "U401") (pin "2") (pinfunction "(AD1.7/CAP0.0/MAT0.0)P0.22_2") (pintype "bidirectional"))
    )
    (net (code "59") (name "unconnected-(U401-(CAP1.3{slash}MISO1{slash}MAT1.3)P0.18-Pad53)") (class "Default")
      (node (ref "U401") (pin "53") (pinfunction "(CAP1.3/MISO1/MAT1.3)P0.18_53") (pintype "bidirectional"))
    )
    (net (code "60") (name "unconnected-(U401-(CTS1{slash}CAP1.1{slash}SCL1)P0.11-Pad37)") (class "Default")
      (node (ref "U401") (pin "37") (pinfunction "(CTS1/CAP1.1/SCL1)P0.11_37") (pintype "bidirectional"))
    )
    (net (code "61") (name "unconnected-(U401-(DSR1{slash}MAT1.0{slash}AD1.3)P0.12-Pad38)") (class "Default")
      (node (ref "U401") (pin "38") (pinfunction "(DSR1/MAT1.0/AD1.3)P0.12_38") (pintype "bidirectional"))
    )
    (net (code "62") (name "unconnected-(U401-(DTR1{slash}MAT1.1{slash}AD1.4)P0.13-Pad39)") (class "Default")
      (node (ref "U401") (pin "39") (pinfunction "(DTR1/MAT1.1/AD1.4)P0.13_39") (pintype "bidirectional"))
    )
    (net (code "63") (name "unconnected-(U401-(EINT0{slash}MAT0.2{slash}CAP0.2)P0.16-Pad46)") (class "Default")
      (node (ref "U401") (pin "46") (pinfunction "(EINT0/MAT0.2/CAP0.2)P0.16_46") (pintype "bidirectional"))
    )
    (net (code "64") (name "unconnected-(U401-(MAT1.2{slash}MOSI1{slash}CAP1.2)P0.19-Pad54)") (class "Default")
      (node (ref "U401") (pin "54") (pinfunction "(MAT1.2/MOSI1/CAP1.2)P0.19_54") (pintype "bidirectional"))
    )
    (net (code "65") (name "unconnected-(U401-(MAT1.3{slash}SSEL1{slash}EINT3)P0.20-Pad55)") (class "Default")
      (node (ref "U401") (pin "55") (pinfunction "(MAT1.3/SSEL1/EINT3)P0.20_55") (pintype "bidirectional"))
    )
    (net (code "66") (name "unconnected-(U401-(PWM5{slash}AD1.6{slash}CAP1.3)P0.21-Pad1)") (class "Default")
      (node (ref "U401") (pin "1") (pinfunction "(PWM5/AD1.6/CAP1.3)P0.21_1") (pintype "bidirectional"))
    )
    (net (code "67") (name "unconnected-(U401-P1.16(TRACEPKT0)-Pad16)") (class "Default")
      (node (ref "U401") (pin "16") (pinfunction "P1.16(TRACEPKT0)_16") (pintype "bidirectional"))
    )
    (net (code "68") (name "unconnected-(U401-P1.17(TRACEPKT1)-Pad12)") (class "Default")
      (node (ref "U401") (pin "12") (pinfunction "P1.17(TRACEPKT1)_12") (pintype "bidirectional"))
    )
    (net (code "69") (name "unconnected-(U401-P1.18(TRACEPKT2)-Pad8)") (class "Default")
      (node (ref "U401") (pin "8") (pinfunction "P1.18(TRACEPKT2)_8") (pintype "bidirectional"))
    )
    (net (code "70") (name "unconnected-(U401-P1.19(TRACEPKT3)-Pad4)") (class "Default")
      (node (ref "U401") (pin "4") (pinfunction "P1.19(TRACEPKT3)_4") (pintype "bidirectional"))
    )
    (net (code "71") (name "unconnected-(U401-P1.20(TRACESYNC)-Pad48)") (class "Default")
      (node (ref "U401") (pin "48") (pinfunction "P1.20(TRACESYNC)_48") (pintype "bidirectional"))
    )
    (net (code "72") (name "unconnected-(U401-P1.21(PIPESTAT0)-Pad44)") (class "Default")
      (node (ref "U401") (pin "44") (pinfunction "P1.21(PIPESTAT0)_44") (pintype "bidirectional"))
    )
    (net (code "73") (name "unconnected-(U401-P1.22(PIPESTAT1)-Pad40)") (class "Default")
      (node (ref "U401") (pin "40") (pinfunction "P1.22(PIPESTAT1)_40") (pintype "bidirectional"))
    )
    (net (code "74") (name "unconnected-(U401-P1.23(PIPESTAT2)-Pad36)") (class "Default")
      (node (ref "U401") (pin "36") (pinfunction "P1.23(PIPESTAT2)_36") (pintype "bidirectional"))
    )
    (net (code "75") (name "unconnected-(U401-P1.24(TRACECLK)-Pad32)") (class "Default")
      (node (ref "U401") (pin "32") (pinfunction "P1.24(TRACECLK)_32") (pintype "bidirectional"))
    )
    (net (code "76") (name "unconnected-(U401-P1.25(EXTIN0)-Pad28)") (class "Default")
      (node (ref "U401") (pin "28") (pinfunction "P1.25(EXTIN0)_28") (pintype "bidirectional"))
    )
    (net (code "77") (name "unconnected-(U401-P1.26(RTCK)-Pad24)") (class "Default")
      (node (ref "U401") (pin "24") (pinfunction "P1.26(RTCK)_24") (pintype "bidirectional"))
    )
    (net (code "78") (name "unconnected-(U401-P1.27(TDO)-Pad64)") (class "Default")
      (node (ref "U401") (pin "64") (pinfunction "P1.27(TDO)_64") (pintype "bidirectional"))
    )
    (net (code "79") (name "unconnected-(U401-P1.28(TDI)-Pad60)") (class "Default")
      (node (ref "U401") (pin "60") (pinfunction "P1.28(TDI)_60") (pintype "bidirectional"))
    )
    (net (code "80") (name "unconnected-(U401-P1.29(TCK)-Pad56)") (class "Default")
      (node (ref "U401") (pin "56") (pinfunction "P1.29(TCK)_56") (pintype "bidirectional"))
    )
    (net (code "81") (name "unconnected-(U401-P1.30(TMS)-Pad52)") (class "Default")
      (node (ref "U401") (pin "52") (pinfunction "P1.30(TMS)_52") (pintype "bidirectional"))
    )
    (net (code "82") (name "unconnected-(U401-P1.31({slash}TRST)-Pad20)") (class "Default")
      (node (ref "U401") (pin "20") (pinfunction "P1.31(/TRST)_20") (pintype "bidirectional"))
    )
    (net (code "83") (name "unconnected-(U601-CLKOUT-Pad22)") (class "Default")
      (node (ref "U601") (pin "22") (pinfunction "CLKOUT_22") (pintype "bidirectional"))
    )
    (net (code "84") (name "unconnected-(U601-ES_CL-Pad7)") (class "Default")
      (node (ref "U601") (pin "7") (pinfunction "ES_CL_7") (pintype "bidirectional"))
    )
    (net (code "85") (name "unconnected-(U601-ES_DA-Pad6)") (class "Default")
      (node (ref "U601") (pin "6") (pinfunction "ES_DA_6") (pintype "bidirectional"))
    )
    (net (code "86") (name "unconnected-(U801-NC-Pad3)") (class "Default")
      (node (ref "U801") (pin "3") (pinfunction "NC_3") (pintype "bidirectional"))
    )
    (net (code "87") (name "unconnected-(U801-NC-Pad5)") (class "Default")
      (node (ref "U801") (pin "5") (pinfunction "NC_5") (pintype "bidirectional"))
    )
    (net (code "88") (name "unconnected-(U801-NC-Pad6)") (class "Default")
      (node (ref "U801") (pin "6") (pinfunction "NC_6") (pintype "bidirectional"))
    )
    (net (code "89") (name "unconnected-(U801-NC-Pad7)") (class "Default")
      (node (ref "U801") (pin "7") (pinfunction "NC_7") (pintype "bidirectional"))
    )
    (net (code "90") (name "unconnected-(U801-NC-Pad14)") (class "Default")
      (node (ref "U801") (pin "14") (pinfunction "NC_14") (pintype "bidirectional"))
    )
  )
)
